# 09_EMC-Power.net
KiCad netlist of a schematic drawn in Altium Designer
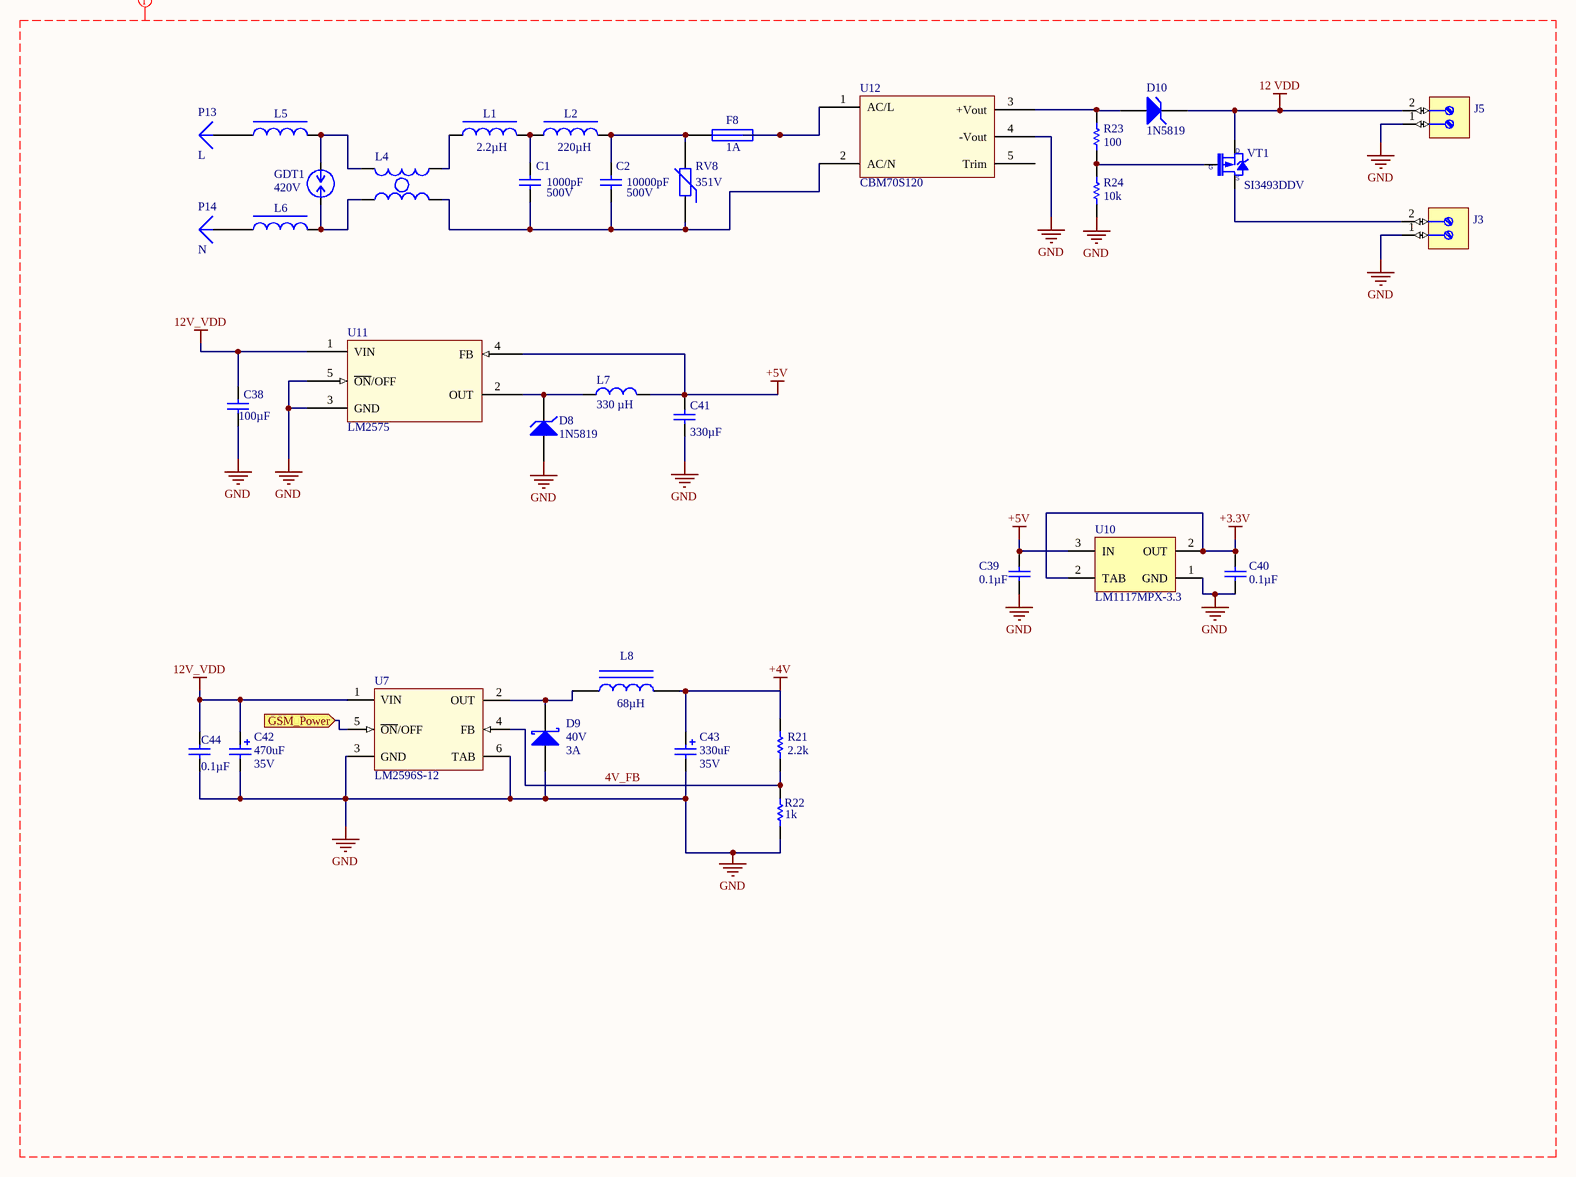
[diagram p0: [09] EMC-Power.SchDoc]

(export (version "E")
  (design (tool "Eeschema 10.0.6"))
  (components
    (comp (ref "C1")
      (value "Capacitor")
      (footprint "Cap 1206")
      (description "Chip Capacitor Nonpolar")
      (fields
        (field (name "MANUFACTURER") "Samsung Electro-Mechanics America, Inc")
        (field (name "MANUFACTURER PART NUMBER") "CL31B102KGFNFNE")
        (field (name "CAPACITANCE") "1000pF")
        (field (name "VOLTAGE - RATED") "500V")
        (field (name "PUBLISHER") "Altium Limited")
      )
      (libsource (lib "Altium_Library") (part "Capacitor"))
    )
    (comp (ref "C2")
      (value "Capacitor")
      (footprint "Cap 1206")
      (description "Chip Capacitor Nonpolar")
      (fields
        (field (name "MANUFACTURER") "Samsung Electro-Mechanics America, Inc")
        (field (name "MANUFACTURER PART NUMBER") "CL31B103KGFNNNE")
        (field (name "CAPACITANCE") "10000pF")
        (field (name "VOLTAGE - RATED") "500V")
      )
      (libsource (lib "Altium_Library") (part "Capacitor"))
    )
    (comp (ref "C38")
      (value "100µF")
      (footprint "Cap 0603")
      (description "Capacitor 0603")
      (fields
        (field (name "MANUFACTURER") "Kemet")
        (field (name "MANUFACTURER PART NUMBER") "C0603C473K5RACTU")
      )
      (libsource (lib "Altium_Library") (part "Capacitor"))
    )
    (comp (ref "C39")
      (value "Capacitor")
      (footprint "Cap 0603")
      (description "Chip Capacitor Nonpolar")
      (fields
        (field (name "MANUFACTURER") "Kemet")
        (field (name "MANUFACTURER PART NUMBER") "C0603C104K5RACTU")
        (field (name "CAPACITANCE") "0.1µF")
      )
      (libsource (lib "Altium_Library") (part "Capacitor"))
    )
    (comp (ref "C40")
      (value "Capacitor")
      (footprint "Cap 0603")
      (description "Chip Capacitor Nonpolar")
      (fields
        (field (name "MANUFACTURER") "Kemet")
        (field (name "MANUFACTURER PART NUMBER") "C0603C104K5RACTU")
        (field (name "CAPACITANCE") "0.1µF")
      )
      (libsource (lib "Altium_Library") (part "Capacitor"))
    )
    (comp (ref "C41")
      (value "330µF")
      (footprint "Cap 0603")
      (description "Capacitor 0603")
      (fields
        (field (name "MANUFACTURER") "Kemet")
        (field (name "MANUFACTURER PART NUMBER") "C0603C473K5RACTU")
      )
      (libsource (lib "Altium_Library") (part "Capacitor"))
    )
    (comp (ref "C42")
      (value "Capacitor Polarized")
      (footprint "Aluminium SMD G")
      (description "Aluminium SMD Capacitors")
      (fields
        (field (name "MANUFACTURER") "Nichicon")
        (field (name "MANUFACTURER PART NUMBER") "UCL1V471MNL1GS")
        (field (name "CAPACITANCE") "470uF")
        (field (name "VOLTAGE RATING") "35V")
      )
      (libsource (lib "Altium_Library") (part "Capacitor Polarized"))
    )
    (comp (ref "C43")
      (value "Capacitor Polarized")
      (footprint "Aluminium SMD G")
      (description "Aluminium SMD Capacitors")
      (fields
        (field (name "MANUFACTURER") "Panasonic")
        (field (name "MANUFACTURER PART NUMBER") "EEE-1VA331P")
        (field (name "CAPACITANCE") "330uF")
        (field (name "VOLTAGE") "35V")
      )
      (libsource (lib "Altium_Library") (part "Capacitor Polarized"))
    )
    (comp (ref "C44")
      (value "Capacitor")
      (footprint "Cap 0603")
      (description "Chip Capacitor Nonpolar")
      (fields
        (field (name "MANUFACTURER") "Kemet")
        (field (name "MANUFACTURER PART NUMBER") "C0603C104K5RACTU")
        (field (name "CAPACITANCE") "0.1µF")
      )
      (libsource (lib "Altium_Library") (part "Capacitor"))
    )
    (comp (ref "D8")
      (value "1N5819")
      (footprint "D100")
      (description "Zener Diode")
      (fields (field (name "PUBLISHER") "Altium Limited"))
      (libsource (lib "MyLib") (part "D Zener"))
    )
    (comp (ref "D9")
      (value "SK32")
      (footprint "SMA")
      (description "Schottky Rectifier")
      (fields
        (field (name "MANUFACTURER") "Diodes")
        (field (name "MANUFACTURER PART NUMBER") "B340A-13-F")
        (field (name "OUTPUT CURRENT") "3A")
        (field (name "VOLTAGE") "40V")
      )
      (libsource (lib "GSMInformer-PB-TC.v1.0-2013") (part "SK32"))
    )
    (comp (ref "D10")
      (value "1N5819")
      (footprint "D100")
      (description "Zener Diode")
      (fields (field (name "PUBLISHER") "Altium Limited"))
      (libsource (lib "MyLib") (part "D Zener"))
    )
    (comp (ref "F8")
      (value "1A")
      (footprint "Fuse")
      (description "Fuse")
      (fields
        (field (name "MANUFACTURER") "TE Connectivity Raychem Circuit Protection")
        (field (name "MANUFACTURER PART NUMBER") "LVR100S")
      )
      (libsource (lib "Altium_Library") (part "Fuse"))
    )
    (comp (ref "GDT1")
      (value "Gas Discharge Tube")
      (footprint "GDT")
      (fields
        (field (name "MANUFACTURER") "TE Connectivity Raychem Circuit Protection")
        (field (name "MANUFACTURER PART NUMBER") "GTCA28-421M-R05")
        (field (name "VOLTAGE - DC SPARK OVER (NOM)") "420V")
        (field (name "TOLERANCE") "±20%")
      )
      (libsource (lib "Altium_Library") (part "Gas Discharge Tube"))
    )
    (comp (ref "J3")
      (value "~")
      (footprint "PHOENIX_1715721")
      (description "Terminal Block, 2 Positions, Screw Connection")
      (fields
        (field (name "PART NUMBER") "PHOENIX_1715721")
        (field (name "MANUFACTURER") "PHOENIX CONTACT")
        (field (name "AUTHOR") "CERN DEM JLC")
      )
      (libsource (lib "Connectors") (part "Terminal Block_2 Positions_Screw Connection"))
    )
    (comp (ref "J5")
      (value "~")
      (footprint "PHOENIX_1715721")
      (description "Terminal Block, 2 Positions, Screw Connection")
      (fields
        (field (name "PART NUMBER") "PHOENIX_1715721")
        (field (name "MANUFACTURER") "PHOENIX CONTACT")
        (field (name "AUTHOR") "CERN DEM JLC")
      )
      (libsource (lib "Connectors") (part "Terminal Block_2 Positions_Screw Connection"))
    )
    (comp (ref "L1")
      (value "Inductor")
      (footprint "Inductor VLS")
      (description "Inductors throgh hole")
      (fields
        (field (name "MANUFACTURER") "TDK Corporation")
        (field (name "MANUFACTURER PART NUMBER") "VLS252012T-2R2M1R3")
        (field (name "INDUCTANCE") "2.2µH")
      )
      (libsource (lib "Altium_Library") (part "InductorCore"))
    )
    (comp (ref "L2")
      (value "Inductor")
      (footprint "SRR1260")
      (description "Inductors throgh hole")
      (fields
        (field (name "MANUFACTURER") "Bourns Inc.")
        (field (name "MANUFACTURER PART NUMBER") "SRR1260-221K")
        (field (name "INDUCTANCE") "220µH")
      )
      (libsource (lib "Altium_Library") (part "InductorCore"))
    )
    (comp (ref "L4")
      (value "Current-compensated Chokes")
      (footprint "RN114_PM3700")
      (description "Current-compensated Chokes RN114")
      (fields
        (field (name "MANUFACTURER") "Schaffner EMC Inc")
        (field (name "MANUFACTURER PART NUMBER") "RN114-1-02")
      )
      (libsource (lib "Altium_Library") (part "Current-compensated Chokes"))
    )
    (comp (ref "L5")
      (value "Inductor")
      (footprint "Inductors:FB20022-4B-RC")
      (description "Inductors throgh hole")
      (fields
        (field (name "MANUFACTURER") "Bourns Inc.")
        (field (name "MANUFACTURER PART NUMBER") "FB20022-4B-RC")
      )
      (libsource (lib "Altium_Library") (part "InductorCore"))
    )
    (comp (ref "L6")
      (value "Inductor")
      (footprint "Inductors:FB20022-4B-RC")
      (description "Inductors throgh hole")
      (fields
        (field (name "MANUFACTURER") "Bourns Inc.")
        (field (name "MANUFACTURER PART NUMBER") "FB20022-4B-RC")
      )
      (libsource (lib "Altium_Library") (part "InductorCore"))
    )
    (comp (ref "L7")
      (value "330 µH")
      (footprint "IND4")
      (description "Inductor")
      (libsource (lib "MyLib") (part "Inductor"))
    )
    (comp (ref "L8")
      (value "SRR1210")
      (footprint "SRR1208")
      (description "Magnetic-Core Inductor")
      (fields
        (field (name "MANUFACTURER") "Bourns Inc.")
        (field (name "MANUFACTURER PART NUMBER") "SRR1210-680M")
        (field (name "INDUCTANCE") "68µH")
        (field (name "PUBLISHER") "Altium Limited")
      )
      (libsource (lib "GSMInformer-PB-TC.v1.0-2013") (part "SRR1210"))
    )
    (comp (ref "P13")
      (value "L")
      (footprint "Socket")
      (description "Plug")
      (fields (field (name "PUBLISHER") "Altium Limited"))
      (libsource (lib "Miscellaneous Connectors") (part "Plug"))
    )
    (comp (ref "P14")
      (value "N")
      (footprint "Socket")
      (description "Plug")
      (fields (field (name "PUBLISHER") "Altium Limited"))
      (libsource (lib "Miscellaneous Connectors") (part "Plug"))
    )
    (comp (ref "R21")
      (value "Res1")
      (footprint "Res-0603")
      (description "Chip Resistor")
      (fields
        (field (name "MANUFACTURER") "Panasonic")
        (field (name "MANUFACTURER PART NUMBER") "ERJ-3GEYJ222V")
        (field (name "RESISTANCE") "2.2k")
      )
      (libsource (lib "Altium_Library") (part "Res1"))
    )
    (comp (ref "R22")
      (value "Res1")
      (footprint "Res-0603")
      (description "Chip Resistor")
      (fields
        (field (name "MANUFACTURER") "Panasonic")
        (field (name "MANUFACTURER PART NUMBER") "ERJ-3GEYJ102V")
        (field (name "RESISTANCE") "1k")
      )
      (libsource (lib "Altium_Library") (part "Res1"))
    )
    (comp (ref "R23")
      (value "Res1")
      (footprint "Res-0603")
      (description "Chip Resistor")
      (fields
        (field (name "MANUFACTURER") "Panasonic")
        (field (name "MANUFACTURER PART NUMBER") "ERJ-3GEYJ222V")
        (field (name "RESISTANCE") "100")
      )
      (libsource (lib "Altium_Library") (part "Res1"))
    )
    (comp (ref "R24")
      (value "Res1")
      (footprint "Res-0603")
      (description "Chip Resistor")
      (fields
        (field (name "MANUFACTURER") "Panasonic")
        (field (name "MANUFACTURER PART NUMBER") "ERJ-3GEYJ222V")
        (field (name "RESISTANCE") "10k")
      )
      (libsource (lib "Altium_Library") (part "Res1"))
    )
    (comp (ref "RV8")
      (value "Res Varistor")
      (footprint "S14k250")
      (fields
        (field (name "MANUFACTURER") "EPCOS Inc")
        (field (name "MANUFACTURER PART NUMBER") "S14K250")
        (field (name "VARISTOR VOLTAGE (MIN)") "351V")
        (field (name "PUBLISHER") "Altium Limited")
      )
      (libsource (lib "Altium_Library") (part "Res Varistor"))
    )
    (comp (ref "U7") (value "LM2596S-12") (libsource (lib "Blue Tractor-2021") (part "LM2596S-12")))
    (comp (ref "U10")
      (value "LM1117MPX-3.3")
      (footprint "SOT-223")
      (description "800mA Low-Dropout Linear Regulator, 4-pin SOT-223")
      (fields
        (field (name "MANUFACTURER") "Texas Instruments")
        (field (name "MANUFACTURER PART NUMBER") "LM1117MPX-3.3/NOPB")
      )
      (libsource (lib "NSC LDO") (part "LM1117MPX-3.3"))
    )
    (comp (ref "U11") (value "LM2575") (libsource (lib "Blue Tractor-2021") (part "LM2575")))
    (comp (ref "U12")
      (value "CBM70S120")
      (description "AC-DC ~230-12")
      (libsource (lib "Blue Tractor-2021") (part "CBM70S120"))
    )
    (comp (ref "VT1")
      (value "SI3493DDV")
      (description "P-Channel 20-V MOSFET")
      (libsource (lib "Blue Tractor-2021") (part "SI3493DVV-T1-GE3"))
    )
  )
  (nets
    (net (code "1") (name "+3.3V") (class "Default")
      (node (ref "C40") (pin "2") (pinfunction "2_2") (pintype "passive"))
      (node (ref "U10") (pin "2") (pinfunction "TAB_2") (pintype "power_in"))
    )
    (net (code "2") (name "+4V") (class "Default")
      (node (ref "C43") (pin "1") (pinfunction "1_1") (pintype "passive"))
      (node (ref "L8") (pin "2") (pinfunction "2_2") (pintype "passive"))
      (node (ref "R21") (pin "1") (pinfunction "1_1") (pintype "passive"))
    )
    (net (code "3") (name "+5V") (class "Default")
      (node (ref "C39") (pin "2") (pinfunction "2_2") (pintype "passive"))
      (node (ref "C41") (pin "2") (pinfunction "2_2") (pintype "passive"))
      (node (ref "L7") (pin "2") (pinfunction "2_2") (pintype "passive"))
      (node (ref "U10") (pin "3") (pinfunction "IN_3") (pintype "power_in"))
      (node (ref "U11") (pin "4") (pinfunction "FB_4") (pintype "input"))
    )
    (net (code "4") (name "/4V_FB") (class "Default")
      (node (ref "R21") (pin "2") (pinfunction "2_2") (pintype "passive"))
      (node (ref "R22") (pin "2") (pinfunction "2_2") (pintype "passive"))
      (node (ref "U7") (pin "4") (pinfunction "FB_4") (pintype "input"))
    )
    (net (code "5") (name "/GSM_Power") (class "Default")
      (node (ref "U7") (pin "5") (pinfunction "~{ON}/OFF_5") (pintype "input"))
    )
    (net (code "6") (name "12 VDD") (class "Default")
      (node (ref "D10") (pin "2") (pinfunction "K_2") (pintype "passive"))
      (node (ref "J5") (pin "2") (pinfunction "2_2") (pintype "bidirectional"))
      (node (ref "VT1") (pin "16") (pinfunction "16_16") (pintype "passive"))
    )
    (net (code "7") (name "12V_VDD") (class "Default")
      (node (ref "C38") (pin "2") (pinfunction "2_2") (pintype "passive"))
      (node (ref "C42") (pin "1") (pinfunction "1_1") (pintype "passive"))
      (node (ref "C44") (pin "2") (pinfunction "2_2") (pintype "passive"))
      (node (ref "U11") (pin "1") (pinfunction "VIN_1") (pintype "power_in"))
      (node (ref "U7") (pin "1") (pinfunction "VIN_1") (pintype "power_in"))
    )
    (net (code "8") (name "GND") (class "Default")
      (node (ref "C38") (pin "1") (pinfunction "1_1") (pintype "passive"))
      (node (ref "C39") (pin "1") (pinfunction "1_1") (pintype "passive"))
      (node (ref "C40") (pin "1") (pinfunction "1_1") (pintype "passive"))
      (node (ref "C41") (pin "1") (pinfunction "1_1") (pintype "passive"))
      (node (ref "C42") (pin "2") (pinfunction "2_2") (pintype "passive"))
      (node (ref "C43") (pin "2") (pinfunction "2_2") (pintype "passive"))
      (node (ref "C44") (pin "1") (pinfunction "1_1") (pintype "passive"))
      (node (ref "D8") (pin "1") (pinfunction "A_1") (pintype "passive"))
      (node (ref "D9") (pin "1") (pinfunction "A_1") (pintype "passive"))
      (node (ref "J3") (pin "1") (pinfunction "1_1") (pintype "bidirectional"))
      (node (ref "J5") (pin "1") (pinfunction "1_1") (pintype "bidirectional"))
      (node (ref "R22") (pin "1") (pinfunction "1_1") (pintype "passive"))
      (node (ref "R24") (pin "2") (pinfunction "2_2") (pintype "passive"))
      (node (ref "U10") (pin "1") (pinfunction "GND_1") (pintype "power_in"))
      (node (ref "U11") (pin "3") (pinfunction "GND_3") (pintype "power_in"))
      (node (ref "U11") (pin "5") (pinfunction "~{ON}/OFF_5") (pintype "input"))
      (node (ref "U12") (pin "4") (pinfunction "-Vout_4") (pintype "power_in"))
      (node (ref "U7") (pin "3") (pinfunction "GND_3") (pintype "power_in"))
      (node (ref "U7") (pin "6") (pinfunction "TAB_6") (pintype "power_in"))
    )
    (net (code "9") (name "Net-(C1-Pad2)") (class "Default")
      (node (ref "C1") (pin "2") (pinfunction "2_2") (pintype "passive"))
      (node (ref "L1") (pin "2") (pinfunction "2_2") (pintype "passive"))
      (node (ref "L2") (pin "1") (pinfunction "1_1") (pintype "passive"))
    )
    (net (code "10") (name "Net-(C2-Pad2)") (class "Default")
      (node (ref "C2") (pin "2") (pinfunction "2_2") (pintype "passive"))
      (node (ref "F8") (pin "1") (pinfunction "1_1") (pintype "passive"))
      (node (ref "L2") (pin "2") (pinfunction "2_2") (pintype "passive"))
      (node (ref "RV8") (pin "2") (pinfunction "2_2") (pintype "passive"))
    )
    (net (code "11") (name "Net-(D8-K)") (class "Default")
      (node (ref "D8") (pin "2") (pinfunction "K_2") (pintype "passive"))
      (node (ref "L7") (pin "1") (pinfunction "1_1") (pintype "passive"))
      (node (ref "U11") (pin "2") (pinfunction "OUT_2") (pintype "power_in"))
    )
    (net (code "12") (name "Net-(D9-K)") (class "Default")
      (node (ref "D9") (pin "2") (pinfunction "K_2") (pintype "passive"))
      (node (ref "L8") (pin "1") (pinfunction "1_1") (pintype "passive"))
      (node (ref "U7") (pin "2") (pinfunction "OUT_2") (pintype "power_in"))
    )
    (net (code "13") (name "Net-(D10-A)") (class "Default")
      (node (ref "D10") (pin "1") (pinfunction "A_1") (pintype "passive"))
      (node (ref "R23") (pin "1") (pinfunction "1_1") (pintype "passive"))
      (node (ref "U12") (pin "3") (pinfunction "+Vout_3") (pintype "power_in"))
    )
    (net (code "14") (name "Net-(GDT1-Pad1)") (class "Default")
      (node (ref "GDT1") (pin "1") (pinfunction "1_1") (pintype "passive"))
      (node (ref "L4") (pin "3") (pinfunction "3_3") (pintype "passive"))
      (node (ref "L5") (pin "2") (pinfunction "2_2") (pintype "passive"))
    )
    (net (code "15") (name "Net-(GDT1-Pad2)") (class "Default")
      (node (ref "GDT1") (pin "2") (pinfunction "2_2") (pintype "passive"))
      (node (ref "L4") (pin "1") (pinfunction "1_1") (pintype "passive"))
      (node (ref "L6") (pin "2") (pinfunction "2_2") (pintype "passive"))
    )
    (net (code "16") (name "Net-(J3-Pad2)") (class "Default")
      (node (ref "J3") (pin "2") (pinfunction "2_2") (pintype "bidirectional"))
      (node (ref "VT1") (pin "17") (pinfunction "17_17") (pintype "passive"))
    )
    (net (code "17") (name "Net-(L1-Pad1)") (class "Default")
      (node (ref "L1") (pin "1") (pinfunction "1_1") (pintype "passive"))
      (node (ref "L4") (pin "4") (pinfunction "4_4") (pintype "passive"))
    )
    (net (code "18") (name "Net-(L5-Pad1)") (class "Default")
      (node (ref "L5") (pin "1") (pinfunction "1_1") (pintype "passive"))
      (node (ref "P13") (pin "1") (pinfunction "1_1") (pintype "passive"))
    )
    (net (code "19") (name "Net-(L6-Pad1)") (class "Default")
      (node (ref "L6") (pin "1") (pinfunction "1_1") (pintype "passive"))
      (node (ref "P14") (pin "1") (pinfunction "1_1") (pintype "passive"))
    )
    (net (code "20") (name "Net-(U12-AC{slash}L)") (class "Default")
      (node (ref "F8") (pin "2") (pinfunction "2_2") (pintype "passive"))
      (node (ref "U12") (pin "1") (pinfunction "AC/L_1") (pintype "power_in"))
    )
    (net (code "21") (name "Net-(U12-AC{slash}N)") (class "Default")
      (node (ref "C1") (pin "1") (pinfunction "1_1") (pintype "passive"))
      (node (ref "C2") (pin "1") (pinfunction "1_1") (pintype "passive"))
      (node (ref "L4") (pin "2") (pinfunction "2_2") (pintype "passive"))
      (node (ref "RV8") (pin "1") (pinfunction "1_1") (pintype "passive"))
      (node (ref "U12") (pin "2") (pinfunction "AC/N_2") (pintype "power_in"))
    )
    (net (code "22") (name "Net-(VT1-PG)") (class "Default")
      (node (ref "R23") (pin "2") (pinfunction "2_2") (pintype "passive"))
      (node (ref "R24") (pin "1") (pinfunction "1_1") (pintype "passive"))
      (node (ref "VT1") (pin "15") (pinfunction "PG_15") (pintype "passive"))
    )
    (net (code "23") (name "unconnected-(U12-Trim-Pad5)") (class "Default")
      (node (ref "U12") (pin "5") (pinfunction "Trim_5") (pintype "passive"))
    )
  )
)
